# cw-twostage-standard.net
KiCad netlist of a schematic drawn in EAGLE
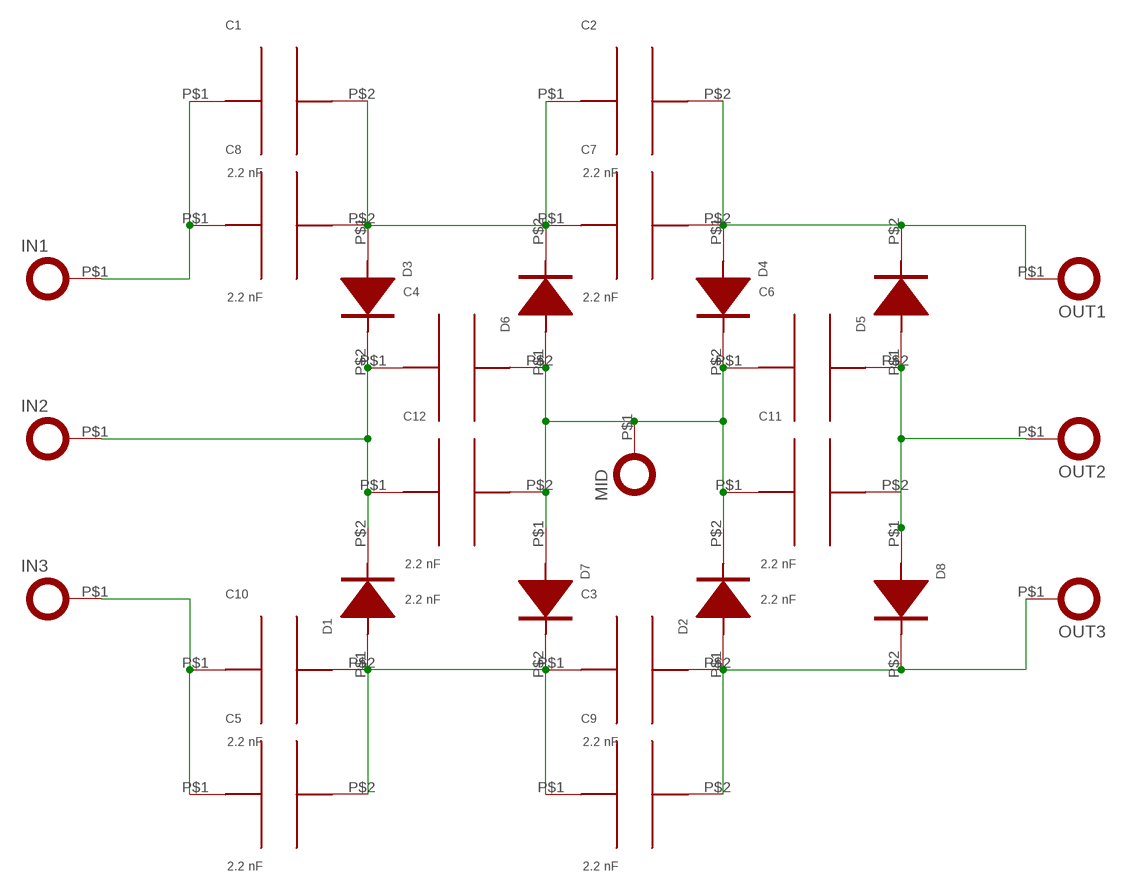
[diagram p0: schematic, sheet 1]

(export (version "E")
  (design (tool "Eeschema 10.0.6"))
  (components
    (comp (ref "C1")
      (value "2.2 nF")
      (footprint "eagle-import:CAP_CT81_12")
      (libsource (lib "eagle-import") (part "HV_CAPACITOR_12MM"))
    )
    (comp (ref "C2")
      (value "2.2 nF")
      (footprint "eagle-import:CAP_CT81_12")
      (libsource (lib "eagle-import") (part "HV_CAPACITOR_12MM"))
    )
    (comp (ref "C3")
      (value "2.2 nF")
      (footprint "eagle-import:CAP_CT81_12")
      (libsource (lib "eagle-import") (part "HV_CAPACITOR_12MM"))
    )
    (comp (ref "C4")
      (value "2.2 nF")
      (footprint "eagle-import:CAP_CT81_12")
      (libsource (lib "eagle-import") (part "HV_CAPACITOR_12MM"))
    )
    (comp (ref "C5")
      (value "2.2 nF")
      (footprint "eagle-import:CAP_CT81_12")
      (libsource (lib "eagle-import") (part "HV_CAPACITOR_12MM"))
    )
    (comp (ref "C6")
      (value "2.2 nF")
      (footprint "eagle-import:CAP_CT81_12")
      (libsource (lib "eagle-import") (part "HV_CAPACITOR_12MM"))
    )
    (comp (ref "C7")
      (value "2.2 nF")
      (footprint "eagle-import:CAP_CT81_12")
      (libsource (lib "eagle-import") (part "HV_CAPACITOR_12MM"))
    )
    (comp (ref "C8")
      (value "2.2 nF")
      (footprint "eagle-import:CAP_CT81_12")
      (libsource (lib "eagle-import") (part "HV_CAPACITOR_12MM"))
    )
    (comp (ref "C9")
      (value "2.2 nF")
      (footprint "eagle-import:CAP_CT81_12")
      (libsource (lib "eagle-import") (part "HV_CAPACITOR_12MM"))
    )
    (comp (ref "C10")
      (value "2.2 nF")
      (footprint "eagle-import:CAP_CT81_12")
      (libsource (lib "eagle-import") (part "HV_CAPACITOR_12MM"))
    )
    (comp (ref "C11")
      (value "2.2 nF")
      (footprint "eagle-import:CAP_CT81_12")
      (libsource (lib "eagle-import") (part "HV_CAPACITOR_12MM"))
    )
    (comp (ref "C12")
      (value "2.2 nF")
      (footprint "eagle-import:CAP_CT81_12")
      (libsource (lib "eagle-import") (part "HV_CAPACITOR_12MM"))
    )
    (comp (ref "D1")
      (value "DIODE_14MM")
      (footprint "eagle-import:DIODE_14")
      (libsource (lib "eagle-import") (part "DIODE_14MM"))
    )
    (comp (ref "D2")
      (value "DIODE_14MM")
      (footprint "eagle-import:DIODE_14")
      (libsource (lib "eagle-import") (part "DIODE_14MM"))
    )
    (comp (ref "D3")
      (value "DIODE_14MM")
      (footprint "eagle-import:DIODE_14")
      (libsource (lib "eagle-import") (part "DIODE_14MM"))
    )
    (comp (ref "D4")
      (value "DIODE_14MM")
      (footprint "eagle-import:DIODE_14")
      (libsource (lib "eagle-import") (part "DIODE_14MM"))
    )
    (comp (ref "D5")
      (value "DIODE_14MM")
      (footprint "eagle-import:DIODE_14")
      (libsource (lib "eagle-import") (part "DIODE_14MM"))
    )
    (comp (ref "D6")
      (value "DIODE_14MM")
      (footprint "eagle-import:DIODE_14")
      (libsource (lib "eagle-import") (part "DIODE_14MM"))
    )
    (comp (ref "D7")
      (value "DIODE_14MM")
      (footprint "eagle-import:DIODE_14")
      (libsource (lib "eagle-import") (part "DIODE_14MM"))
    )
    (comp (ref "D8")
      (value "DIODE_14MM")
      (footprint "eagle-import:DIODE_14")
      (libsource (lib "eagle-import") (part "DIODE_14MM"))
    )
    (comp (ref "IN1")
      (value "TERMINAL_M6")
      (footprint "eagle-import:LUG_SQUARE_M6")
      (libsource (lib "eagle-import") (part "TERMINAL_M6"))
    )
    (comp (ref "IN2")
      (value "TERMINAL_M6")
      (footprint "eagle-import:LUG_SQUARE_M6")
      (libsource (lib "eagle-import") (part "TERMINAL_M6"))
    )
    (comp (ref "IN3")
      (value "TERMINAL_M6")
      (footprint "eagle-import:LUG_SQUARE_M6")
      (libsource (lib "eagle-import") (part "TERMINAL_M6"))
    )
    (comp (ref "MID")
      (value "TERMINAL_M6")
      (footprint "eagle-import:LUG_SQUARE_M6")
      (libsource (lib "eagle-import") (part "TERMINAL_M6"))
    )
    (comp (ref "OUT1")
      (value "TERMINAL_M6")
      (footprint "eagle-import:LUG_SQUARE_M6")
      (libsource (lib "eagle-import") (part "TERMINAL_M6"))
    )
    (comp (ref "OUT2")
      (value "TERMINAL_M6")
      (footprint "eagle-import:LUG_SQUARE_M6")
      (libsource (lib "eagle-import") (part "TERMINAL_M6"))
    )
    (comp (ref "OUT3")
      (value "TERMINAL_M6")
      (footprint "eagle-import:LUG_SQUARE_M6")
      (libsource (lib "eagle-import") (part "TERMINAL_M6"))
    )
  )
  (nets
    (net (code "1") (name "Net-(C1-PadP$1)") (class "Default")
      (node (ref "C1") (pin "P$1") (pinfunction "P$1_P$1") (pintype "passive"))
      (node (ref "C8") (pin "P$1") (pinfunction "P$1_P$1") (pintype "passive"))
      (node (ref "IN1") (pin "P$1") (pinfunction "P$1_P$1") (pintype "passive"))
    )
    (net (code "2") (name "Net-(C10-PadP$1)") (class "Default")
      (node (ref "C10") (pin "P$1") (pinfunction "P$1_P$1") (pintype "passive"))
      (node (ref "C5") (pin "P$1") (pinfunction "P$1_P$1") (pintype "passive"))
      (node (ref "IN3") (pin "P$1") (pinfunction "P$1_P$1") (pintype "passive"))
    )
    (net (code "3") (name "Net-(D1-ANODE)") (class "Default")
      (node (ref "C10") (pin "P$2") (pinfunction "P$2_P$2") (pintype "passive"))
      (node (ref "C3") (pin "P$1") (pinfunction "P$1_P$1") (pintype "passive"))
      (node (ref "C5") (pin "P$2") (pinfunction "P$2_P$2") (pintype "passive"))
      (node (ref "C9") (pin "P$1") (pinfunction "P$1_P$1") (pintype "passive"))
      (node (ref "D1") (pin "P$1") (pinfunction "ANODE_P$1") (pintype "passive"))
      (node (ref "D7") (pin "P$2") (pinfunction "CATHODE_P$2") (pintype "passive"))
    )
    (net (code "4") (name "Net-(D1-CATHODE)") (class "Default")
      (node (ref "C12") (pin "P$1") (pinfunction "P$1_P$1") (pintype "passive"))
      (node (ref "C4") (pin "P$1") (pinfunction "P$1_P$1") (pintype "passive"))
      (node (ref "D1") (pin "P$2") (pinfunction "CATHODE_P$2") (pintype "passive"))
      (node (ref "D3") (pin "P$2") (pinfunction "CATHODE_P$2") (pintype "passive"))
      (node (ref "IN2") (pin "P$1") (pinfunction "P$1_P$1") (pintype "passive"))
    )
    (net (code "5") (name "Net-(D2-ANODE)") (class "Default")
      (node (ref "C3") (pin "P$2") (pinfunction "P$2_P$2") (pintype "passive"))
      (node (ref "C9") (pin "P$2") (pinfunction "P$2_P$2") (pintype "passive"))
      (node (ref "D2") (pin "P$1") (pinfunction "ANODE_P$1") (pintype "passive"))
      (node (ref "D8") (pin "P$2") (pinfunction "CATHODE_P$2") (pintype "passive"))
      (node (ref "OUT3") (pin "P$1") (pinfunction "P$1_P$1") (pintype "passive"))
    )
    (net (code "6") (name "Net-(D2-CATHODE)") (class "Default")
      (node (ref "C11") (pin "P$1") (pinfunction "P$1_P$1") (pintype "passive"))
      (node (ref "C12") (pin "P$2") (pinfunction "P$2_P$2") (pintype "passive"))
      (node (ref "C4") (pin "P$2") (pinfunction "P$2_P$2") (pintype "passive"))
      (node (ref "C6") (pin "P$1") (pinfunction "P$1_P$1") (pintype "passive"))
      (node (ref "D2") (pin "P$2") (pinfunction "CATHODE_P$2") (pintype "passive"))
      (node (ref "D4") (pin "P$2") (pinfunction "CATHODE_P$2") (pintype "passive"))
      (node (ref "D6") (pin "P$1") (pinfunction "ANODE_P$1") (pintype "passive"))
      (node (ref "D7") (pin "P$1") (pinfunction "ANODE_P$1") (pintype "passive"))
      (node (ref "MID") (pin "P$1") (pinfunction "P$1_P$1") (pintype "passive"))
    )
    (net (code "7") (name "Net-(D3-ANODE)") (class "Default")
      (node (ref "C1") (pin "P$2") (pinfunction "P$2_P$2") (pintype "passive"))
      (node (ref "C2") (pin "P$1") (pinfunction "P$1_P$1") (pintype "passive"))
      (node (ref "C7") (pin "P$1") (pinfunction "P$1_P$1") (pintype "passive"))
      (node (ref "C8") (pin "P$2") (pinfunction "P$2_P$2") (pintype "passive"))
      (node (ref "D3") (pin "P$1") (pinfunction "ANODE_P$1") (pintype "passive"))
      (node (ref "D6") (pin "P$2") (pinfunction "CATHODE_P$2") (pintype "passive"))
    )
    (net (code "8") (name "Net-(D4-ANODE)") (class "Default")
      (node (ref "C2") (pin "P$2") (pinfunction "P$2_P$2") (pintype "passive"))
      (node (ref "C7") (pin "P$2") (pinfunction "P$2_P$2") (pintype "passive"))
      (node (ref "D4") (pin "P$1") (pinfunction "ANODE_P$1") (pintype "passive"))
      (node (ref "D5") (pin "P$2") (pinfunction "CATHODE_P$2") (pintype "passive"))
      (node (ref "OUT1") (pin "P$1") (pinfunction "P$1_P$1") (pintype "passive"))
    )
    (net (code "9") (name "Net-(D5-ANODE)") (class "Default")
      (node (ref "C11") (pin "P$2") (pinfunction "P$2_P$2") (pintype "passive"))
      (node (ref "C6") (pin "P$2") (pinfunction "P$2_P$2") (pintype "passive"))
      (node (ref "D5") (pin "P$1") (pinfunction "ANODE_P$1") (pintype "passive"))
      (node (ref "D8") (pin "P$1") (pinfunction "ANODE_P$1") (pintype "passive"))
      (node (ref "OUT2") (pin "P$1") (pinfunction "P$1_P$1") (pintype "passive"))
    )
  )
)
